# STSPIN32F0A_ESC3.net
KiCad netlist of a schematic drawn in Altium Designer
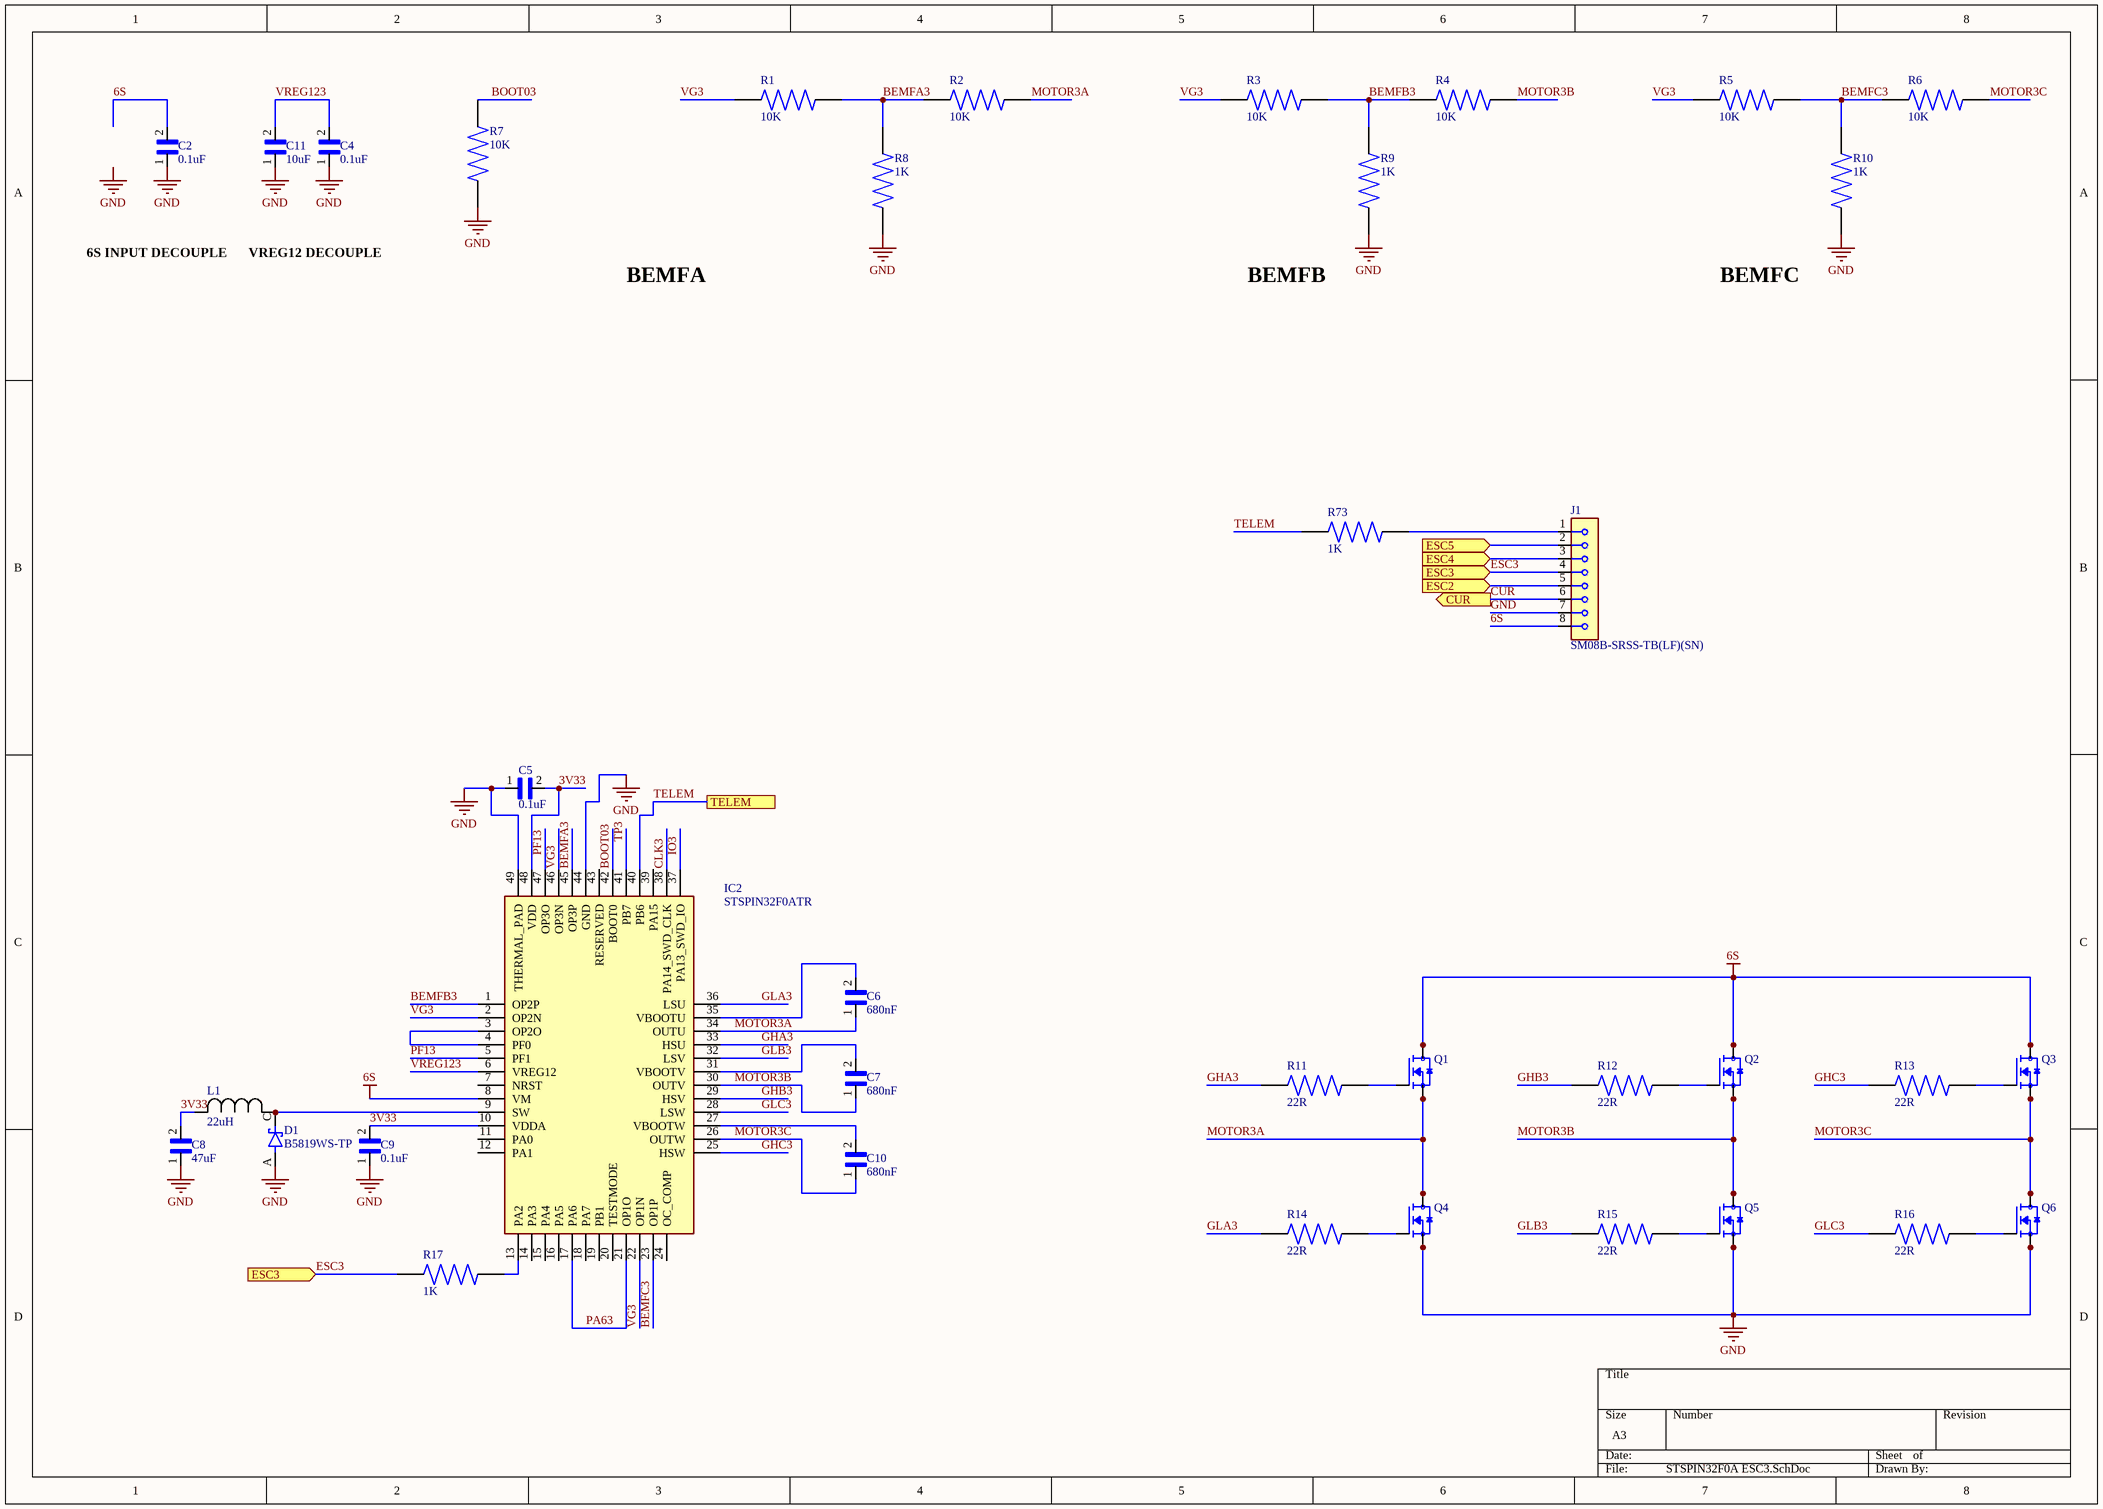
[diagram p0: STSPIN32F0A ESC3.SchDoc]

(export (version "E")
  (design (tool "Eeschema 10.0.6"))
  (components
    (comp (ref "C2")
      (value "0.1uF")
      (footprint "CAPC1005X55N")
      (fields (field (name "MP") "GRM1555C1H222JA01D"))
      (libsource (lib "GRM1555C1H222JA01D") (part "GRM1555C1H222JA01D"))
    )
    (comp (ref "C4")
      (value "0.1uF")
      (footprint "CAPC1005X55N")
      (fields (field (name "MP") "GRM1555C1H222JA01D"))
      (libsource (lib "GRM1555C1H222JA01D") (part "GRM1555C1H222JA01D"))
    )
    (comp (ref "C5")
      (value "0.1uF")
      (footprint "CAPC1005X55N")
      (fields (field (name "MP") "GRM1555C1H222JA01D"))
      (libsource (lib "") (part "GRM1555C1H222JA01D_1"))
    )
    (comp (ref "C6")
      (value "680nF")
      (footprint "CAPC1005X55N")
      (fields (field (name "MP") "GRM1555C1H222JA01D"))
      (libsource (lib "GRM1555C1H222JA01D") (part "GRM1555C1H222JA01D"))
    )
    (comp (ref "C7")
      (value "680nF")
      (footprint "CAPC1005X55N")
      (fields (field (name "MP") "GRM1555C1H222JA01D"))
      (libsource (lib "GRM1555C1H222JA01D") (part "GRM1555C1H222JA01D"))
    )
    (comp (ref "C8")
      (value "47uF")
      (footprint "CAPC1608X90N")
      (description "SMD Capacitor X7R(EIA) with Capacitance: 0.22uF Tol. 5%. Rated Voltage: 25Vdc")
      (fields (field (name "MP") "GRM188R71E224JA88D"))
      (libsource (lib "GRM188R71E224JA88D") (part "GRM188R71E224JA88D"))
    )
    (comp (ref "C9")
      (value "0.1uF")
      (footprint "CAPC1005X55N")
      (fields (field (name "MP") "GRM1555C1H222JA01D"))
      (libsource (lib "GRM1555C1H222JA01D") (part "GRM1555C1H222JA01D"))
    )
    (comp (ref "C10")
      (value "680nF")
      (footprint "CAPC1005X55N")
      (fields (field (name "MP") "GRM1555C1H222JA01D"))
      (libsource (lib "GRM1555C1H222JA01D") (part "GRM1555C1H222JA01D"))
    )
    (comp (ref "C11")
      (value "10uF")
      (footprint "CAPC1608X90N")
      (description "SMD Capacitor X7R(EIA) with Capacitance: 0.22uF Tol. 5%. Rated Voltage: 25Vdc")
      (fields (field (name "MP") "GRM188R71E224JA88D"))
      (libsource (lib "GRM188R71E224JA88D") (part "GRM188R71E224JA88D"))
    )
    (comp (ref "D1")
      (value "B5819WS-TP")
      (footprint "SOD2512X115N")
      (fields (field (name "MF") "{'manufacturer': u'Micro Commercial Components'}"))
      (libsource (lib "SnapEDA_Library") (part "B5819WS-TP"))
    )
    (comp (ref "IC2")
      (value "STSPIN32F0ATR")
      (footprint "SamacSys:QFN50P700X700X100-49N-D")
      (description "Integrated Circuit")
      (fields (field (name "MOUSER PART NUMBER") "511-STSPIN32F0ATR"))
      (libsource (lib "SamacSys") (part "STSPIN32F0ATR"))
    )
    (comp (ref "J1")
      (value "SM08B-SRSS-TB(LF)(SN)")
      (footprint "JST_SM08B-SRSS-TB(LF)(SN)")
      (description "SH Series 8 Position 1 mm Pitch Surface Mount Side Entry Shrouded Header")
      (libsource (lib "SM08B-SRSS-TB_LF__SN_") (part "SM08B-SRSS-TB(LF)(SN)"))
    )
    (comp (ref "L1")
      (value "22uH")
      (footprint "IND_BOURNS_SRN3015")
      (description "No Description Available")
      (fields
        (field (name "MANUFACTURER_PART_NUMBER") "SRN3015-220M")
        (field (name "COPYRIGHT") "Copyright (C) 2022 Ultra Librarian. All rights reserved.")
      )
      (libsource (lib "SRN3015-220M") (part "SRN3015-220M"))
    )
    (comp (ref "Q1")
      (value "TPHR8504PL,L1Q")
      (footprint "TRANS_TPHR8504PL,L1Q")
      (description "N-Channel 40V 150A (Tc) 1W (Ta), 170W (Tc) Surface Mount 8-SOP Advance (5x5)")
      (fields (field (name "MF") "Toshiba Semiconductor"))
      (libsource (lib "TPHR8504PL_L1Q") (part "TPHR8504PL,L1Q"))
    )
    (comp (ref "Q2")
      (value "TPHR8504PL,L1Q")
      (footprint "TRANS_TPHR8504PL,L1Q")
      (description "N-Channel 40V 150A (Tc) 1W (Ta), 170W (Tc) Surface Mount 8-SOP Advance (5x5)")
      (fields (field (name "MF") "Toshiba Semiconductor"))
      (libsource (lib "TPHR8504PL_L1Q") (part "TPHR8504PL,L1Q"))
    )
    (comp (ref "Q3")
      (value "TPHR8504PL,L1Q")
      (footprint "TRANS_TPHR8504PL,L1Q")
      (description "N-Channel 40V 150A (Tc) 1W (Ta), 170W (Tc) Surface Mount 8-SOP Advance (5x5)")
      (fields (field (name "MF") "Toshiba Semiconductor"))
      (libsource (lib "TPHR8504PL_L1Q") (part "TPHR8504PL,L1Q"))
    )
    (comp (ref "Q4")
      (value "TPHR8504PL,L1Q")
      (footprint "TRANS_TPHR8504PL,L1Q")
      (description "N-Channel 40V 150A (Tc) 1W (Ta), 170W (Tc) Surface Mount 8-SOP Advance (5x5)")
      (fields (field (name "MF") "Toshiba Semiconductor"))
      (libsource (lib "TPHR8504PL_L1Q") (part "TPHR8504PL,L1Q"))
    )
    (comp (ref "Q5")
      (value "TPHR8504PL,L1Q")
      (footprint "TRANS_TPHR8504PL,L1Q")
      (description "N-Channel 40V 150A (Tc) 1W (Ta), 170W (Tc) Surface Mount 8-SOP Advance (5x5)")
      (fields (field (name "MF") "Toshiba Semiconductor"))
      (libsource (lib "TPHR8504PL_L1Q") (part "TPHR8504PL,L1Q"))
    )
    (comp (ref "Q6")
      (value "TPHR8504PL,L1Q")
      (footprint "TRANS_TPHR8504PL,L1Q")
      (description "N-Channel 40V 150A (Tc) 1W (Ta), 170W (Tc) Surface Mount 8-SOP Advance (5x5)")
      (fields (field (name "MF") "Toshiba Semiconductor"))
      (libsource (lib "TPHR8504PL_L1Q") (part "TPHR8504PL,L1Q"))
    )
    (comp (ref "R1")
      (value "10K")
      (footprint "RESC1005X37N")
      (fields (field (name "MP") "RE0402BRE07330KL") (field (name "MF") "{'manufacturer': u'Yageo'}"))
      (libsource (lib "SnapEDA_Library") (part "RE0402BRE07330KL"))
    )
    (comp (ref "R2")
      (value "10K")
      (footprint "RESC1005X37N")
      (fields (field (name "MP") "RE0402BRE07330KL") (field (name "MF") "{'manufacturer': u'Yageo'}"))
      (libsource (lib "SnapEDA_Library") (part "RE0402BRE07330KL"))
    )
    (comp (ref "R3")
      (value "10K")
      (footprint "RESC1005X37N")
      (fields (field (name "MP") "RE0402BRE07330KL") (field (name "MF") "{'manufacturer': u'Yageo'}"))
      (libsource (lib "SnapEDA_Library") (part "RE0402BRE07330KL"))
    )
    (comp (ref "R4")
      (value "10K")
      (footprint "RESC1005X37N")
      (fields (field (name "MP") "RE0402BRE07330KL") (field (name "MF") "{'manufacturer': u'Yageo'}"))
      (libsource (lib "SnapEDA_Library") (part "RE0402BRE07330KL"))
    )
    (comp (ref "R5")
      (value "10K")
      (footprint "RESC1005X37N")
      (fields (field (name "MP") "RE0402BRE07330KL") (field (name "MF") "{'manufacturer': u'Yageo'}"))
      (libsource (lib "SnapEDA_Library") (part "RE0402BRE07330KL"))
    )
    (comp (ref "R6")
      (value "10K")
      (footprint "RESC1005X37N")
      (fields (field (name "MP") "RE0402BRE07330KL") (field (name "MF") "{'manufacturer': u'Yageo'}"))
      (libsource (lib "SnapEDA_Library") (part "RE0402BRE07330KL"))
    )
    (comp (ref "R7")
      (value "10K")
      (footprint "RESC1005X37N")
      (fields (field (name "MP") "RE0402BRE07330KL") (field (name "MF") "{'manufacturer': u'Yageo'}"))
      (libsource (lib "SnapEDA_Library") (part "RE0402BRE07330KL"))
    )
    (comp (ref "R8")
      (value "1K")
      (footprint "RESC1005X37N")
      (fields (field (name "MP") "RE0402BRE07330KL") (field (name "MF") "{'manufacturer': u'Yageo'}"))
      (libsource (lib "SnapEDA_Library") (part "RE0402BRE07330KL"))
    )
    (comp (ref "R9")
      (value "1K")
      (footprint "RESC1005X37N")
      (fields (field (name "MP") "RE0402BRE07330KL") (field (name "MF") "{'manufacturer': u'Yageo'}"))
      (libsource (lib "SnapEDA_Library") (part "RE0402BRE07330KL"))
    )
    (comp (ref "R10")
      (value "1K")
      (footprint "RESC1005X37N")
      (fields (field (name "MP") "RE0402BRE07330KL") (field (name "MF") "{'manufacturer': u'Yageo'}"))
      (libsource (lib "SnapEDA_Library") (part "RE0402BRE07330KL"))
    )
    (comp (ref "R11")
      (value "22R")
      (footprint "RESC1005X37N")
      (fields (field (name "MP") "RE0402BRE07330KL") (field (name "MF") "{'manufacturer': u'Yageo'}"))
      (libsource (lib "SnapEDA_Library") (part "RE0402BRE07330KL"))
    )
    (comp (ref "R12")
      (value "22R")
      (footprint "RESC1005X37N")
      (fields (field (name "MP") "RE0402BRE07330KL") (field (name "MF") "{'manufacturer': u'Yageo'}"))
      (libsource (lib "SnapEDA_Library") (part "RE0402BRE07330KL"))
    )
    (comp (ref "R13")
      (value "22R")
      (footprint "RESC1005X37N")
      (fields (field (name "MP") "RE0402BRE07330KL") (field (name "MF") "{'manufacturer': u'Yageo'}"))
      (libsource (lib "SnapEDA_Library") (part "RE0402BRE07330KL"))
    )
    (comp (ref "R14")
      (value "22R")
      (footprint "RESC1005X37N")
      (fields (field (name "MP") "RE0402BRE07330KL") (field (name "MF") "{'manufacturer': u'Yageo'}"))
      (libsource (lib "SnapEDA_Library") (part "RE0402BRE07330KL"))
    )
    (comp (ref "R15")
      (value "22R")
      (footprint "RESC1005X37N")
      (fields (field (name "MP") "RE0402BRE07330KL") (field (name "MF") "{'manufacturer': u'Yageo'}"))
      (libsource (lib "SnapEDA_Library") (part "RE0402BRE07330KL"))
    )
    (comp (ref "R16")
      (value "22R")
      (footprint "RESC1005X37N")
      (fields (field (name "MP") "RE0402BRE07330KL") (field (name "MF") "{'manufacturer': u'Yageo'}"))
      (libsource (lib "SnapEDA_Library") (part "RE0402BRE07330KL"))
    )
    (comp (ref "R17")
      (value "1K")
      (footprint "RESC1005X37N")
      (fields (field (name "MP") "RE0402BRE07330KL") (field (name "MF") "{'manufacturer': u'Yageo'}"))
      (libsource (lib "SnapEDA_Library") (part "RE0402BRE07330KL"))
    )
    (comp (ref "R73")
      (value "1K")
      (footprint "RESC1005X37N")
      (fields (field (name "MP") "RE0402BRE07330KL") (field (name "MF") "{'manufacturer': u'Yageo'}"))
      (libsource (lib "SnapEDA_Library") (part "RE0402BRE07330KL"))
    )
  )
  (nets
    (net (code "1") (name "/3V33") (class "Default")
      (node (ref "C5") (pin "2") (pinfunction "2_2") (pintype "passive"))
      (node (ref "C8") (pin "2") (pinfunction "2_2") (pintype "passive"))
      (node (ref "C9") (pin "2") (pinfunction "2_2") (pintype "passive"))
      (node (ref "IC2") (pin "10") (pinfunction "VDDA_10") (pintype "passive"))
      (node (ref "IC2") (pin "48") (pinfunction "VDD_48") (pintype "passive"))
      (node (ref "L1") (pin "2") (pinfunction "2_2") (pintype "passive"))
    )
    (net (code "2") (name "/BEMFA3") (class "Default")
      (node (ref "IC2") (pin "45") (pinfunction "OP3P_45") (pintype "passive"))
      (node (ref "R1") (pin "1") (pinfunction "1_1") (pintype "passive"))
      (node (ref "R2") (pin "2") (pinfunction "2_2") (pintype "passive"))
      (node (ref "R8") (pin "1") (pinfunction "1_1") (pintype "passive"))
    )
    (net (code "3") (name "/BEMFB3") (class "Default")
      (node (ref "IC2") (pin "1") (pinfunction "OP2P_1") (pintype "passive"))
      (node (ref "R3") (pin "1") (pinfunction "1_1") (pintype "passive"))
      (node (ref "R4") (pin "2") (pinfunction "2_2") (pintype "passive"))
      (node (ref "R9") (pin "1") (pinfunction "1_1") (pintype "passive"))
    )
    (net (code "4") (name "/BEMFC3") (class "Default")
      (node (ref "IC2") (pin "23") (pinfunction "OP1P_23") (pintype "passive"))
      (node (ref "R10") (pin "1") (pinfunction "1_1") (pintype "passive"))
      (node (ref "R5") (pin "1") (pinfunction "1_1") (pintype "passive"))
      (node (ref "R6") (pin "2") (pinfunction "2_2") (pintype "passive"))
    )
    (net (code "5") (name "/BOOT03") (class "Default")
      (node (ref "IC2") (pin "42") (pinfunction "BOOT0_42") (pintype "passive"))
      (node (ref "R7") (pin "2") (pinfunction "2_2") (pintype "passive"))
    )
    (net (code "6") (name "/CLK3") (class "Default")
      (node (ref "IC2") (pin "38") (pinfunction "PA14_SWD_CLK_38") (pintype "passive"))
    )
    (net (code "7") (name "/CUR") (class "Default")
      (node (ref "J1") (pin "6") (pinfunction "6_6") (pintype "passive"))
    )
    (net (code "8") (name "/ESC2") (class "Default")
      (node (ref "J1") (pin "5") (pinfunction "5_5") (pintype "passive"))
    )
    (net (code "9") (name "/ESC3") (class "Default")
      (node (ref "J1") (pin "4") (pinfunction "4_4") (pintype "passive"))
      (node (ref "R17") (pin "1") (pinfunction "1_1") (pintype "passive"))
    )
    (net (code "10") (name "/ESC4") (class "Default")
      (node (ref "J1") (pin "3") (pinfunction "3_3") (pintype "passive"))
    )
    (net (code "11") (name "/ESC5") (class "Default")
      (node (ref "J1") (pin "2") (pinfunction "2_2") (pintype "passive"))
    )
    (net (code "12") (name "/GHA3") (class "Default")
      (node (ref "IC2") (pin "33") (pinfunction "HSU_33") (pintype "passive"))
      (node (ref "R11") (pin "2") (pinfunction "2_2") (pintype "passive"))
    )
    (net (code "13") (name "/GHB3") (class "Default")
      (node (ref "IC2") (pin "29") (pinfunction "HSV_29") (pintype "passive"))
      (node (ref "R12") (pin "2") (pinfunction "2_2") (pintype "passive"))
    )
    (net (code "14") (name "/GHC3") (class "Default")
      (node (ref "IC2") (pin "25") (pinfunction "HSW_25") (pintype "passive"))
      (node (ref "R13") (pin "2") (pinfunction "2_2") (pintype "passive"))
    )
    (net (code "15") (name "/GLA3") (class "Default")
      (node (ref "IC2") (pin "36") (pinfunction "LSU_36") (pintype "passive"))
      (node (ref "R14") (pin "2") (pinfunction "2_2") (pintype "passive"))
    )
    (net (code "16") (name "/GLB3") (class "Default")
      (node (ref "IC2") (pin "32") (pinfunction "LSV_32") (pintype "passive"))
      (node (ref "R15") (pin "2") (pinfunction "2_2") (pintype "passive"))
    )
    (net (code "17") (name "/GLC3") (class "Default")
      (node (ref "IC2") (pin "28") (pinfunction "LSW_28") (pintype "passive"))
      (node (ref "R16") (pin "2") (pinfunction "2_2") (pintype "passive"))
    )
    (net (code "18") (name "/IO3") (class "Default")
      (node (ref "IC2") (pin "37") (pinfunction "PA13_SWD_IO_37") (pintype "passive"))
    )
    (net (code "19") (name "/MOTOR3A") (class "Default")
      (node (ref "C6") (pin "1") (pinfunction "1_1") (pintype "passive"))
      (node (ref "IC2") (pin "34") (pinfunction "OUTU_34") (pintype "passive"))
      (node (ref "Q1") (pin "1") (pinfunction "S_1") (pintype "passive"))
      (node (ref "Q1") (pin "2") (pinfunction "S_2") (pintype "passive"))
      (node (ref "Q1") (pin "3") (pinfunction "S_3") (pintype "passive"))
      (node (ref "Q4") (pin "5") (pinfunction "D_5") (pintype "passive"))
      (node (ref "Q4") (pin "6") (pinfunction "D_6") (pintype "passive"))
      (node (ref "Q4") (pin "7") (pinfunction "D_7") (pintype "passive"))
      (node (ref "Q4") (pin "8") (pinfunction "D_8") (pintype "passive"))
      (node (ref "Q4") (pin "9") (pinfunction "D_9") (pintype "passive"))
      (node (ref "R2") (pin "1") (pinfunction "1_1") (pintype "passive"))
    )
    (net (code "20") (name "/MOTOR3B") (class "Default")
      (node (ref "C7") (pin "1") (pinfunction "1_1") (pintype "passive"))
      (node (ref "IC2") (pin "30") (pinfunction "OUTV_30") (pintype "passive"))
      (node (ref "Q2") (pin "1") (pinfunction "S_1") (pintype "passive"))
      (node (ref "Q2") (pin "2") (pinfunction "S_2") (pintype "passive"))
      (node (ref "Q2") (pin "3") (pinfunction "S_3") (pintype "passive"))
      (node (ref "Q5") (pin "5") (pinfunction "D_5") (pintype "passive"))
      (node (ref "Q5") (pin "6") (pinfunction "D_6") (pintype "passive"))
      (node (ref "Q5") (pin "7") (pinfunction "D_7") (pintype "passive"))
      (node (ref "Q5") (pin "8") (pinfunction "D_8") (pintype "passive"))
      (node (ref "Q5") (pin "9") (pinfunction "D_9") (pintype "passive"))
      (node (ref "R4") (pin "1") (pinfunction "1_1") (pintype "passive"))
    )
    (net (code "21") (name "/MOTOR3C") (class "Default")
      (node (ref "C10") (pin "1") (pinfunction "1_1") (pintype "passive"))
      (node (ref "IC2") (pin "26") (pinfunction "OUTW_26") (pintype "passive"))
      (node (ref "Q3") (pin "1") (pinfunction "S_1") (pintype "passive"))
      (node (ref "Q3") (pin "2") (pinfunction "S_2") (pintype "passive"))
      (node (ref "Q3") (pin "3") (pinfunction "S_3") (pintype "passive"))
      (node (ref "Q6") (pin "5") (pinfunction "D_5") (pintype "passive"))
      (node (ref "Q6") (pin "6") (pinfunction "D_6") (pintype "passive"))
      (node (ref "Q6") (pin "7") (pinfunction "D_7") (pintype "passive"))
      (node (ref "Q6") (pin "8") (pinfunction "D_8") (pintype "passive"))
      (node (ref "Q6") (pin "9") (pinfunction "D_9") (pintype "passive"))
      (node (ref "R6") (pin "1") (pinfunction "1_1") (pintype "passive"))
    )
    (net (code "22") (name "/PA63") (class "Default")
      (node (ref "IC2") (pin "17") (pinfunction "PA6_17") (pintype "passive"))
      (node (ref "IC2") (pin "21") (pinfunction "OP1O_21") (pintype "passive"))
    )
    (net (code "23") (name "/PF13") (class "Default")
      (node (ref "IC2") (pin "47") (pinfunction "OP3O_47") (pintype "passive"))
      (node (ref "IC2") (pin "5") (pinfunction "PF1_5") (pintype "passive"))
    )
    (net (code "24") (name "/TELEM") (class "Default")
      (node (ref "IC2") (pin "40") (pinfunction "PB6_40") (pintype "passive"))
      (node (ref "R73") (pin "1") (pinfunction "1_1") (pintype "passive"))
    )
    (net (code "25") (name "/TP3") (class "Default")
      (node (ref "IC2") (pin "41") (pinfunction "PB7_41") (pintype "passive"))
    )
    (net (code "26") (name "/VG3") (class "Default")
      (node (ref "IC2") (pin "2") (pinfunction "OP2N_2") (pintype "passive"))
      (node (ref "IC2") (pin "22") (pinfunction "OP1N_22") (pintype "passive"))
      (node (ref "IC2") (pin "46") (pinfunction "OP3N_46") (pintype "passive"))
      (node (ref "R1") (pin "2") (pinfunction "2_2") (pintype "passive"))
      (node (ref "R3") (pin "2") (pinfunction "2_2") (pintype "passive"))
      (node (ref "R5") (pin "2") (pinfunction "2_2") (pintype "passive"))
    )
    (net (code "27") (name "/VREG123") (class "Default")
      (node (ref "C11") (pin "2") (pinfunction "2_2") (pintype "passive"))
      (node (ref "C4") (pin "2") (pinfunction "2_2") (pintype "passive"))
      (node (ref "IC2") (pin "6") (pinfunction "VREG12_6") (pintype "passive"))
    )
    (net (code "28") (name "6S") (class "Default")
      (node (ref "C2") (pin "2") (pinfunction "2_2") (pintype "passive"))
      (node (ref "IC2") (pin "8") (pinfunction "VM_8") (pintype "passive"))
      (node (ref "J1") (pin "8") (pinfunction "8_8") (pintype "passive"))
      (node (ref "Q1") (pin "5") (pinfunction "D_5") (pintype "passive"))
      (node (ref "Q1") (pin "6") (pinfunction "D_6") (pintype "passive"))
      (node (ref "Q1") (pin "7") (pinfunction "D_7") (pintype "passive"))
      (node (ref "Q1") (pin "8") (pinfunction "D_8") (pintype "passive"))
      (node (ref "Q1") (pin "9") (pinfunction "D_9") (pintype "passive"))
      (node (ref "Q2") (pin "5") (pinfunction "D_5") (pintype "passive"))
      (node (ref "Q2") (pin "6") (pinfunction "D_6") (pintype "passive"))
      (node (ref "Q2") (pin "7") (pinfunction "D_7") (pintype "passive"))
      (node (ref "Q2") (pin "8") (pinfunction "D_8") (pintype "passive"))
      (node (ref "Q2") (pin "9") (pinfunction "D_9") (pintype "passive"))
      (node (ref "Q3") (pin "5") (pinfunction "D_5") (pintype "passive"))
      (node (ref "Q3") (pin "6") (pinfunction "D_6") (pintype "passive"))
      (node (ref "Q3") (pin "7") (pinfunction "D_7") (pintype "passive"))
      (node (ref "Q3") (pin "8") (pinfunction "D_8") (pintype "passive"))
      (node (ref "Q3") (pin "9") (pinfunction "D_9") (pintype "passive"))
    )
    (net (code "29") (name "GND") (class "Default")
      (node (ref "C11") (pin "1") (pinfunction "1_1") (pintype "passive"))
      (node (ref "C2") (pin "1") (pinfunction "1_1") (pintype "passive"))
      (node (ref "C4") (pin "1") (pinfunction "1_1") (pintype "passive"))
      (node (ref "C5") (pin "1") (pinfunction "1_1") (pintype "passive"))
      (node (ref "C8") (pin "1") (pinfunction "1_1") (pintype "passive"))
      (node (ref "C9") (pin "1") (pinfunction "1_1") (pintype "passive"))
      (node (ref "D1") (pin "A") (pinfunction "A_A") (pintype "passive"))
      (node (ref "IC2") (pin "44") (pinfunction "GND_44") (pintype "passive"))
      (node (ref "IC2") (pin "49") (pinfunction "THERMAL_PAD_49") (pintype "passive"))
      (node (ref "J1") (pin "7") (pinfunction "7_7") (pintype "passive"))
      (node (ref "Q4") (pin "1") (pinfunction "S_1") (pintype "passive"))
      (node (ref "Q4") (pin "2") (pinfunction "S_2") (pintype "passive"))
      (node (ref "Q4") (pin "3") (pinfunction "S_3") (pintype "passive"))
      (node (ref "Q5") (pin "1") (pinfunction "S_1") (pintype "passive"))
      (node (ref "Q5") (pin "2") (pinfunction "S_2") (pintype "passive"))
      (node (ref "Q5") (pin "3") (pinfunction "S_3") (pintype "passive"))
      (node (ref "Q6") (pin "1") (pinfunction "S_1") (pintype "passive"))
      (node (ref "Q6") (pin "2") (pinfunction "S_2") (pintype "passive"))
      (node (ref "Q6") (pin "3") (pinfunction "S_3") (pintype "passive"))
      (node (ref "R10") (pin "2") (pinfunction "2_2") (pintype "passive"))
      (node (ref "R7") (pin "1") (pinfunction "1_1") (pintype "passive"))
      (node (ref "R8") (pin "2") (pinfunction "2_2") (pintype "passive"))
      (node (ref "R9") (pin "2") (pinfunction "2_2") (pintype "passive"))
    )
    (net (code "30") (name "Net-(D1-K)") (class "Default")
      (node (ref "D1") (pin "C") (pinfunction "K_C") (pintype "passive"))
      (node (ref "IC2") (pin "9") (pinfunction "SW_9") (pintype "passive"))
      (node (ref "L1") (pin "1") (pinfunction "1_1") (pintype "passive"))
    )
    (net (code "31") (name "Net-(IC2-OP2O)") (class "Default")
      (node (ref "IC2") (pin "3") (pinfunction "OP2O_3") (pintype "passive"))
      (node (ref "IC2") (pin "4") (pinfunction "PF0_4") (pintype "passive"))
    )
    (net (code "32") (name "Net-(IC2-PA2)") (class "Default")
      (node (ref "IC2") (pin "13") (pinfunction "PA2_13") (pintype "passive"))
      (node (ref "R17") (pin "2") (pinfunction "2_2") (pintype "passive"))
    )
    (net (code "33") (name "Net-(IC2-VBOOTU)") (class "Default")
      (node (ref "C6") (pin "2") (pinfunction "2_2") (pintype "passive"))
      (node (ref "IC2") (pin "35") (pinfunction "VBOOTU_35") (pintype "passive"))
    )
    (net (code "34") (name "Net-(IC2-VBOOTV)") (class "Default")
      (node (ref "C7") (pin "2") (pinfunction "2_2") (pintype "passive"))
      (node (ref "IC2") (pin "31") (pinfunction "VBOOTV_31") (pintype "passive"))
    )
    (net (code "35") (name "Net-(IC2-VBOOTW)") (class "Default")
      (node (ref "C10") (pin "2") (pinfunction "2_2") (pintype "passive"))
      (node (ref "IC2") (pin "27") (pinfunction "VBOOTW_27") (pintype "passive"))
    )
    (net (code "36") (name "Net-(J1-Pad1)") (class "Default")
      (node (ref "J1") (pin "1") (pinfunction "1_1") (pintype "passive"))
      (node (ref "R73") (pin "2") (pinfunction "2_2") (pintype "passive"))
    )
    (net (code "37") (name "Net-(Q1-G)") (class "Default")
      (node (ref "Q1") (pin "4") (pinfunction "G_4") (pintype "passive"))
      (node (ref "R11") (pin "1") (pinfunction "1_1") (pintype "passive"))
    )
    (net (code "38") (name "Net-(Q2-G)") (class "Default")
      (node (ref "Q2") (pin "4") (pinfunction "G_4") (pintype "passive"))
      (node (ref "R12") (pin "1") (pinfunction "1_1") (pintype "passive"))
    )
    (net (code "39") (name "Net-(Q3-G)") (class "Default")
      (node (ref "Q3") (pin "4") (pinfunction "G_4") (pintype "passive"))
      (node (ref "R13") (pin "1") (pinfunction "1_1") (pintype "passive"))
    )
    (net (code "40") (name "Net-(Q4-G)") (class "Default")
      (node (ref "Q4") (pin "4") (pinfunction "G_4") (pintype "passive"))
      (node (ref "R14") (pin "1") (pinfunction "1_1") (pintype "passive"))
    )
    (net (code "41") (name "Net-(Q5-G)") (class "Default")
      (node (ref "Q5") (pin "4") (pinfunction "G_4") (pintype "passive"))
      (node (ref "R15") (pin "1") (pinfunction "1_1") (pintype "passive"))
    )
    (net (code "42") (name "Net-(Q6-G)") (class "Default")
      (node (ref "Q6") (pin "4") (pinfunction "G_4") (pintype "passive"))
      (node (ref "R16") (pin "1") (pinfunction "1_1") (pintype "passive"))
    )
    (net (code "43") (name "unconnected-(IC2-NRST-Pad7)") (class "Default")
      (node (ref "IC2") (pin "7") (pinfunction "NRST_7") (pintype "passive"))
    )
    (net (code "44") (name "unconnected-(IC2-OC_COMP-Pad24)") (class "Default")
      (node (ref "IC2") (pin "24") (pinfunction "OC_COMP_24") (pintype "passive"))
    )
    (net (code "45") (name "unconnected-(IC2-PA0-Pad11)") (class "Default")
      (node (ref "IC2") (pin "11") (pinfunction "PA0_11") (pintype "passive"))
    )
    (net (code "46") (name "unconnected-(IC2-PA1-Pad12)") (class "Default")
      (node (ref "IC2") (pin "12") (pinfunction "PA1_12") (pintype "passive"))
    )
    (net (code "47") (name "unconnected-(IC2-PA3-Pad14)") (class "Default")
      (node (ref "IC2") (pin "14") (pinfunction "PA3_14") (pintype "passive"))
    )
    (net (code "48") (name "unconnected-(IC2-PA4-Pad15)") (class "Default")
      (node (ref "IC2") (pin "15") (pinfunction "PA4_15") (pintype "passive"))
    )
    (net (code "49") (name "unconnected-(IC2-PA5-Pad16)") (class "Default")
      (node (ref "IC2") (pin "16") (pinfunction "PA5_16") (pintype "passive"))
    )
    (net (code "50") (name "unconnected-(IC2-PA7-Pad18)") (class "Default")
      (node (ref "IC2") (pin "18") (pinfunction "PA7_18") (pintype "passive"))
    )
    (net (code "51") (name "unconnected-(IC2-PA15-Pad39)") (class "Default")
      (node (ref "IC2") (pin "39") (pinfunction "PA15_39") (pintype "passive"))
    )
    (net (code "52") (name "unconnected-(IC2-PB1-Pad19)") (class "Default")
      (node (ref "IC2") (pin "19") (pinfunction "PB1_19") (pintype "passive"))
    )
    (net (code "53") (name "unconnected-(IC2-RESERVED-Pad43)") (class "Default")
      (node (ref "IC2") (pin "43") (pinfunction "RESERVED_43") (pintype "passive"))
    )
    (net (code "54") (name "unconnected-(IC2-TESTMODE-Pad20)") (class "Default")
      (node (ref "IC2") (pin "20") (pinfunction "TESTMODE_20") (pintype "passive"))
    )
  )
)
